# A10-A20-OLINUXINO-MICRO_Extension_Rev_A_.net
KiCad netlist of a schematic drawn in EAGLE
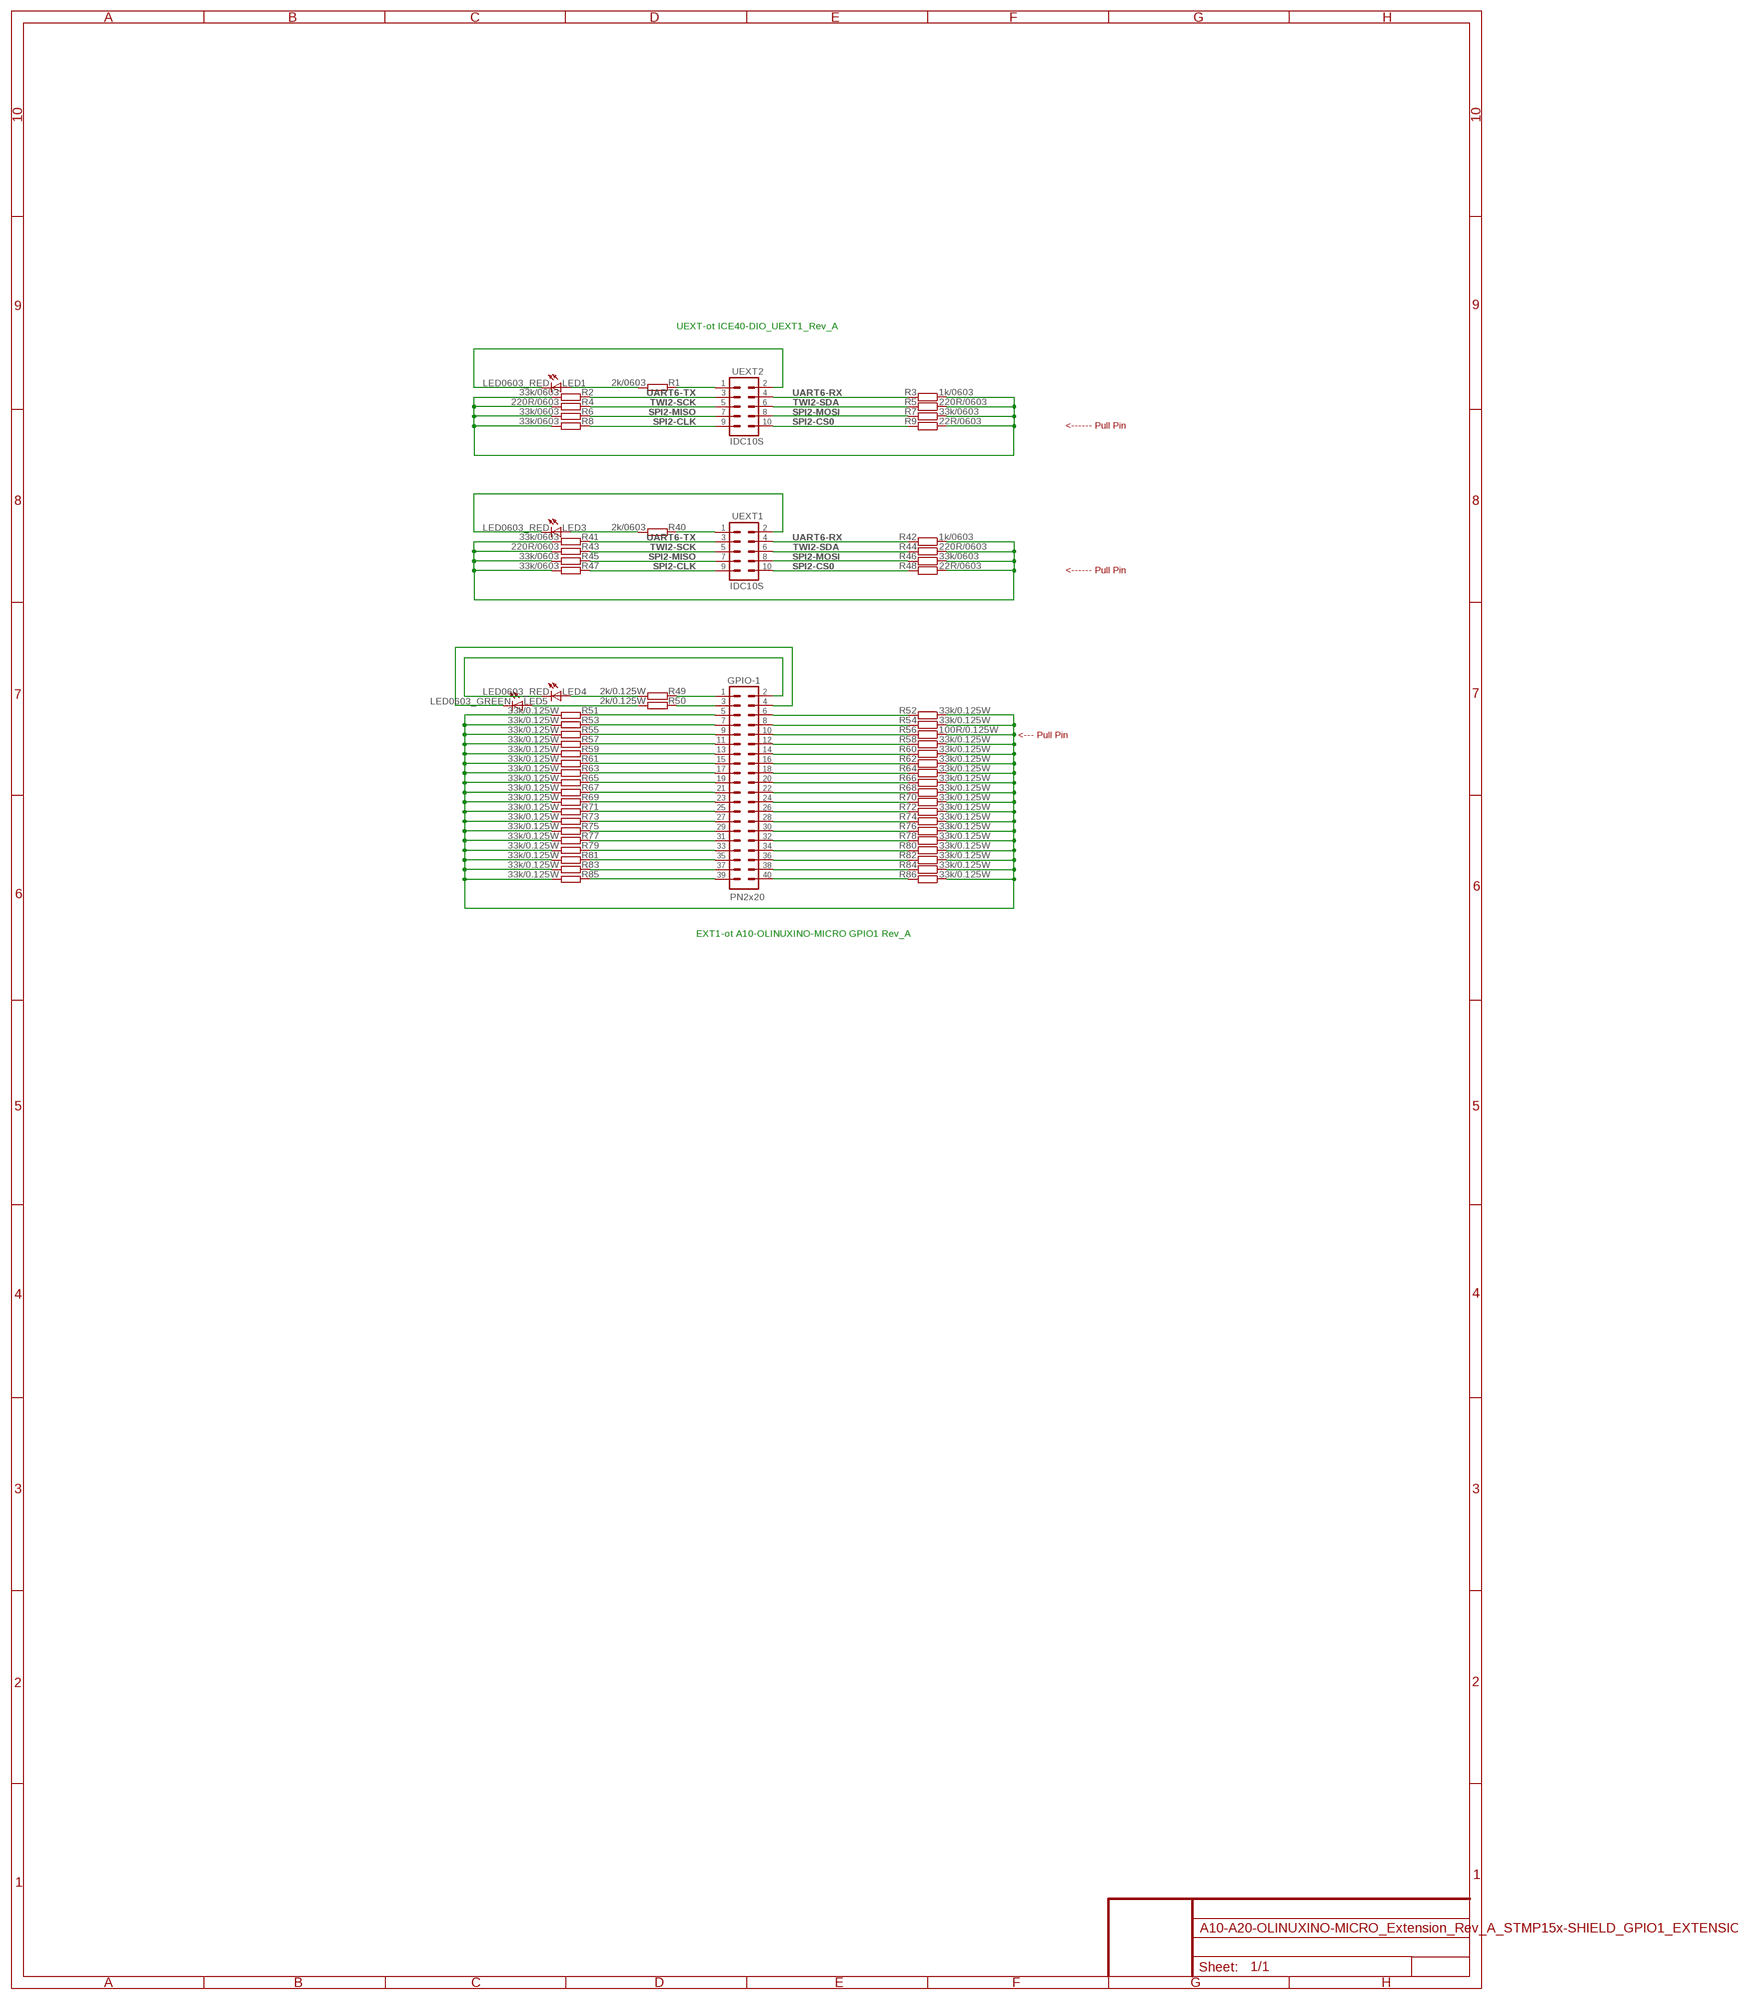
[diagram p0: schematic, sheet 1]

(export (version "E")
  (design (tool "Eeschema 10.0.6"))
  (components
    (comp (ref "GPIO-1")
      (value "PN2x20")
      (footprint "eagle-import:ML40-FEMALE(PN2X20)")
      (libsource (lib "eagle-import") (part "ML40PN2X20"))
    )
    (comp (ref "LED1")
      (value "LED0603_RED")
      (footprint "eagle-import:LED-0603")
      (libsource (lib "eagle-import") (part "LED0603DWS"))
    )
    (comp (ref "LED3")
      (value "LED0603_RED")
      (footprint "eagle-import:LED-0603")
      (libsource (lib "eagle-import") (part "LED0603DWS"))
    )
    (comp (ref "LED4")
      (value "LED0603_RED")
      (footprint "eagle-import:LED-0603")
      (libsource (lib "eagle-import") (part "LED0603DWS"))
    )
    (comp (ref "LED5")
      (value "LED0603_GREEN")
      (footprint "eagle-import:LED-0603")
      (libsource (lib "eagle-import") (part "LED0603DWS"))
    )
    (comp (ref "R1")
      (value "2k/0603")
      (footprint "eagle-import:0204_5")
      (libsource (lib "eagle-import") (part "R-EU_0204/5"))
    )
    (comp (ref "R2")
      (value "33k/0603")
      (footprint "eagle-import:0204_5")
      (libsource (lib "eagle-import") (part "R-EU_0204/5"))
    )
    (comp (ref "R3")
      (value "1k/0603")
      (footprint "eagle-import:0204_5")
      (libsource (lib "eagle-import") (part "R-EU_0204/5"))
    )
    (comp (ref "R4")
      (value "220R/0603")
      (footprint "eagle-import:0204_5")
      (libsource (lib "eagle-import") (part "R-EU_0204/5"))
    )
    (comp (ref "R5")
      (value "220R/0603")
      (footprint "eagle-import:0204_5")
      (libsource (lib "eagle-import") (part "R-EU_0204/5"))
    )
    (comp (ref "R6")
      (value "33k/0603")
      (footprint "eagle-import:0204_5")
      (libsource (lib "eagle-import") (part "R-EU_0204/5"))
    )
    (comp (ref "R7")
      (value "33k/0603")
      (footprint "eagle-import:0204_5")
      (libsource (lib "eagle-import") (part "R-EU_0204/5"))
    )
    (comp (ref "R8")
      (value "33k/0603")
      (footprint "eagle-import:0204_5")
      (libsource (lib "eagle-import") (part "R-EU_0204/5"))
    )
    (comp (ref "R9")
      (value "22R/0603")
      (footprint "eagle-import:0204_5")
      (libsource (lib "eagle-import") (part "R-EU_0204/5"))
    )
    (comp (ref "R40")
      (value "2k/0603")
      (footprint "eagle-import:0204_5")
      (libsource (lib "eagle-import") (part "R-EU_0204/5"))
    )
    (comp (ref "R41")
      (value "33k/0603")
      (footprint "eagle-import:0204_5")
      (libsource (lib "eagle-import") (part "R-EU_0204/5"))
    )
    (comp (ref "R42")
      (value "1k/0603")
      (footprint "eagle-import:0204_5")
      (libsource (lib "eagle-import") (part "R-EU_0204/5"))
    )
    (comp (ref "R43")
      (value "220R/0603")
      (footprint "eagle-import:0204_5")
      (libsource (lib "eagle-import") (part "R-EU_0204/5"))
    )
    (comp (ref "R44")
      (value "220R/0603")
      (footprint "eagle-import:0204_5")
      (libsource (lib "eagle-import") (part "R-EU_0204/5"))
    )
    (comp (ref "R45")
      (value "33k/0603")
      (footprint "eagle-import:0204_5")
      (libsource (lib "eagle-import") (part "R-EU_0204/5"))
    )
    (comp (ref "R46")
      (value "33k/0603")
      (footprint "eagle-import:0204_5")
      (libsource (lib "eagle-import") (part "R-EU_0204/5"))
    )
    (comp (ref "R47")
      (value "33k/0603")
      (footprint "eagle-import:0204_5")
      (libsource (lib "eagle-import") (part "R-EU_0204/5"))
    )
    (comp (ref "R48")
      (value "22R/0603")
      (footprint "eagle-import:0204_5")
      (libsource (lib "eagle-import") (part "R-EU_0204/5"))
    )
    (comp (ref "R49")
      (value "2k/0.125W")
      (footprint "eagle-import:0204_5")
      (libsource (lib "eagle-import") (part "R-EU_0204/5"))
    )
    (comp (ref "R50")
      (value "2k/0.125W")
      (footprint "eagle-import:0204_5")
      (libsource (lib "eagle-import") (part "R-EU_0204/5"))
    )
    (comp (ref "R51")
      (value "33k/0.125W")
      (footprint "eagle-import:0204_5")
      (libsource (lib "eagle-import") (part "R-EU_0204/5"))
    )
    (comp (ref "R52")
      (value "33k/0.125W")
      (footprint "eagle-import:0204_5")
      (libsource (lib "eagle-import") (part "R-EU_0204/5"))
    )
    (comp (ref "R53")
      (value "33k/0.125W")
      (footprint "eagle-import:0204_5")
      (libsource (lib "eagle-import") (part "R-EU_0204/5"))
    )
    (comp (ref "R54")
      (value "33k/0.125W")
      (footprint "eagle-import:0204_5")
      (libsource (lib "eagle-import") (part "R-EU_0204/5"))
    )
    (comp (ref "R55")
      (value "33k/0.125W")
      (footprint "eagle-import:0204_5")
      (libsource (lib "eagle-import") (part "R-EU_0204/5"))
    )
    (comp (ref "R56")
      (value "100R/0.125W")
      (footprint "eagle-import:0204_5")
      (libsource (lib "eagle-import") (part "R-EU_0204/5"))
    )
    (comp (ref "R57")
      (value "33k/0.125W")
      (footprint "eagle-import:0204_5")
      (libsource (lib "eagle-import") (part "R-EU_0204/5"))
    )
    (comp (ref "R58")
      (value "33k/0.125W")
      (footprint "eagle-import:0204_5")
      (libsource (lib "eagle-import") (part "R-EU_0204/5"))
    )
    (comp (ref "R59")
      (value "33k/0.125W")
      (footprint "eagle-import:0204_5")
      (libsource (lib "eagle-import") (part "R-EU_0204/5"))
    )
    (comp (ref "R60")
      (value "33k/0.125W")
      (footprint "eagle-import:0204_5")
      (libsource (lib "eagle-import") (part "R-EU_0204/5"))
    )
    (comp (ref "R61")
      (value "33k/0.125W")
      (footprint "eagle-import:0204_5")
      (libsource (lib "eagle-import") (part "R-EU_0204/5"))
    )
    (comp (ref "R62")
      (value "33k/0.125W")
      (footprint "eagle-import:0204_5")
      (libsource (lib "eagle-import") (part "R-EU_0204/5"))
    )
    (comp (ref "R63")
      (value "33k/0.125W")
      (footprint "eagle-import:0204_5")
      (libsource (lib "eagle-import") (part "R-EU_0204/5"))
    )
    (comp (ref "R64")
      (value "33k/0.125W")
      (footprint "eagle-import:0204_5")
      (libsource (lib "eagle-import") (part "R-EU_0204/5"))
    )
    (comp (ref "R65")
      (value "33k/0.125W")
      (footprint "eagle-import:0204_5")
      (libsource (lib "eagle-import") (part "R-EU_0204/5"))
    )
    (comp (ref "R66")
      (value "33k/0.125W")
      (footprint "eagle-import:0204_5")
      (libsource (lib "eagle-import") (part "R-EU_0204/5"))
    )
    (comp (ref "R67")
      (value "33k/0.125W")
      (footprint "eagle-import:0204_5")
      (libsource (lib "eagle-import") (part "R-EU_0204/5"))
    )
    (comp (ref "R68")
      (value "33k/0.125W")
      (footprint "eagle-import:0204_5")
      (libsource (lib "eagle-import") (part "R-EU_0204/5"))
    )
    (comp (ref "R69")
      (value "33k/0.125W")
      (footprint "eagle-import:0204_5")
      (libsource (lib "eagle-import") (part "R-EU_0204/5"))
    )
    (comp (ref "R70")
      (value "33k/0.125W")
      (footprint "eagle-import:0204_5")
      (libsource (lib "eagle-import") (part "R-EU_0204/5"))
    )
    (comp (ref "R71")
      (value "33k/0.125W")
      (footprint "eagle-import:0204_5")
      (libsource (lib "eagle-import") (part "R-EU_0204/5"))
    )
    (comp (ref "R72")
      (value "33k/0.125W")
      (footprint "eagle-import:0204_5")
      (libsource (lib "eagle-import") (part "R-EU_0204/5"))
    )
    (comp (ref "R73")
      (value "33k/0.125W")
      (footprint "eagle-import:0204_5")
      (libsource (lib "eagle-import") (part "R-EU_0204/5"))
    )
    (comp (ref "R74")
      (value "33k/0.125W")
      (footprint "eagle-import:0204_5")
      (libsource (lib "eagle-import") (part "R-EU_0204/5"))
    )
    (comp (ref "R75")
      (value "33k/0.125W")
      (footprint "eagle-import:0204_5")
      (libsource (lib "eagle-import") (part "R-EU_0204/5"))
    )
    (comp (ref "R76")
      (value "33k/0.125W")
      (footprint "eagle-import:0204_5")
      (libsource (lib "eagle-import") (part "R-EU_0204/5"))
    )
    (comp (ref "R77")
      (value "33k/0.125W")
      (footprint "eagle-import:0204_5")
      (libsource (lib "eagle-import") (part "R-EU_0204/5"))
    )
    (comp (ref "R78")
      (value "33k/0.125W")
      (footprint "eagle-import:0204_5")
      (libsource (lib "eagle-import") (part "R-EU_0204/5"))
    )
    (comp (ref "R79")
      (value "33k/0.125W")
      (footprint "eagle-import:0204_5")
      (libsource (lib "eagle-import") (part "R-EU_0204/5"))
    )
    (comp (ref "R80")
      (value "33k/0.125W")
      (footprint "eagle-import:0204_5")
      (libsource (lib "eagle-import") (part "R-EU_0204/5"))
    )
    (comp (ref "R81")
      (value "33k/0.125W")
      (footprint "eagle-import:0204_5")
      (libsource (lib "eagle-import") (part "R-EU_0204/5"))
    )
    (comp (ref "R82")
      (value "33k/0.125W")
      (footprint "eagle-import:0204_5")
      (libsource (lib "eagle-import") (part "R-EU_0204/5"))
    )
    (comp (ref "R83")
      (value "33k/0.125W")
      (footprint "eagle-import:0204_5")
      (libsource (lib "eagle-import") (part "R-EU_0204/5"))
    )
    (comp (ref "R84")
      (value "33k/0.125W")
      (footprint "eagle-import:0204_5")
      (libsource (lib "eagle-import") (part "R-EU_0204/5"))
    )
    (comp (ref "R85")
      (value "33k/0.125W")
      (footprint "eagle-import:0204_5")
      (libsource (lib "eagle-import") (part "R-EU_0204/5"))
    )
    (comp (ref "R86")
      (value "33k/0.125W")
      (footprint "eagle-import:0204_5")
      (libsource (lib "eagle-import") (part "R-EU_0204/5"))
    )
    (comp (ref "UEXT1")
      (value "IDC10S")
      (footprint "eagle-import:ML10-FEMALE(IDC10S_PCB)")
      (libsource (lib "eagle-import") (part "ML10ML10-FEMALE(IDC10S/PCB)"))
    )
    (comp (ref "UEXT2")
      (value "IDC10S")
      (footprint "eagle-import:ML10-FEMALE(IDC10S_PCB)")
      (libsource (lib "eagle-import") (part "ML10ML10-FEMALE(IDC10S/PCB)"))
    )
  )
  (nets
    (net (code "1") (name "/SPI2-CLK") (class "Default")
      (node (ref "R47") (pin "2") (pinfunction "2_2") (pintype "passive"))
      (node (ref "R8") (pin "2") (pinfunction "2_2") (pintype "passive"))
      (node (ref "UEXT1") (pin "9") (pinfunction "9_9") (pintype "passive"))
      (node (ref "UEXT2") (pin "9") (pinfunction "9_9") (pintype "passive"))
    )
    (net (code "2") (name "/SPI2-CS0") (class "Default")
      (node (ref "R48") (pin "2") (pinfunction "2_2") (pintype "passive"))
      (node (ref "R9") (pin "2") (pinfunction "2_2") (pintype "passive"))
      (node (ref "UEXT1") (pin "10") (pinfunction "10_10") (pintype "passive"))
      (node (ref "UEXT2") (pin "10") (pinfunction "10_10") (pintype "passive"))
    )
    (net (code "3") (name "/SPI2-MISO") (class "Default")
      (node (ref "R45") (pin "2") (pinfunction "2_2") (pintype "passive"))
      (node (ref "R6") (pin "2") (pinfunction "2_2") (pintype "passive"))
      (node (ref "UEXT1") (pin "7") (pinfunction "7_7") (pintype "passive"))
      (node (ref "UEXT2") (pin "7") (pinfunction "7_7") (pintype "passive"))
    )
    (net (code "4") (name "/SPI2-MOSI") (class "Default")
      (node (ref "R46") (pin "2") (pinfunction "2_2") (pintype "passive"))
      (node (ref "R7") (pin "2") (pinfunction "2_2") (pintype "passive"))
      (node (ref "UEXT1") (pin "8") (pinfunction "8_8") (pintype "passive"))
      (node (ref "UEXT2") (pin "8") (pinfunction "8_8") (pintype "passive"))
    )
    (net (code "5") (name "/TWI2-SCK") (class "Default")
      (node (ref "R4") (pin "2") (pinfunction "2_2") (pintype "passive"))
      (node (ref "R43") (pin "2") (pinfunction "2_2") (pintype "passive"))
      (node (ref "UEXT1") (pin "5") (pinfunction "5_5") (pintype "passive"))
      (node (ref "UEXT2") (pin "5") (pinfunction "5_5") (pintype "passive"))
    )
    (net (code "6") (name "/TWI2-SDA") (class "Default")
      (node (ref "R44") (pin "2") (pinfunction "2_2") (pintype "passive"))
      (node (ref "R5") (pin "2") (pinfunction "2_2") (pintype "passive"))
      (node (ref "UEXT1") (pin "6") (pinfunction "6_6") (pintype "passive"))
      (node (ref "UEXT2") (pin "6") (pinfunction "6_6") (pintype "passive"))
    )
    (net (code "7") (name "/UART6-RX") (class "Default")
      (node (ref "R3") (pin "2") (pinfunction "2_2") (pintype "passive"))
      (node (ref "R42") (pin "2") (pinfunction "2_2") (pintype "passive"))
      (node (ref "UEXT1") (pin "4") (pinfunction "4_4") (pintype "passive"))
      (node (ref "UEXT2") (pin "4") (pinfunction "4_4") (pintype "passive"))
    )
    (net (code "8") (name "/UART6-TX") (class "Default")
      (node (ref "R2") (pin "2") (pinfunction "2_2") (pintype "passive"))
      (node (ref "R41") (pin "2") (pinfunction "2_2") (pintype "passive"))
      (node (ref "UEXT1") (pin "3") (pinfunction "3_3") (pintype "passive"))
      (node (ref "UEXT2") (pin "3") (pinfunction "3_3") (pintype "passive"))
    )
    (net (code "9") (name "Net-(GPIO-1-Pad1)") (class "Default")
      (node (ref "GPIO-1") (pin "1") (pinfunction "1_1") (pintype "passive"))
      (node (ref "R49") (pin "2") (pinfunction "2_2") (pintype "passive"))
    )
    (net (code "10") (name "Net-(GPIO-1-Pad2)") (class "Default")
      (node (ref "GPIO-1") (pin "2") (pinfunction "2_2") (pintype "passive"))
      (node (ref "LED4") (pin "C") (pinfunction "C_C") (pintype "passive"))
    )
    (net (code "11") (name "Net-(GPIO-1-Pad3)") (class "Default")
      (node (ref "GPIO-1") (pin "3") (pinfunction "3_3") (pintype "passive"))
      (node (ref "R50") (pin "2") (pinfunction "2_2") (pintype "passive"))
    )
    (net (code "12") (name "Net-(GPIO-1-Pad4)") (class "Default")
      (node (ref "GPIO-1") (pin "4") (pinfunction "4_4") (pintype "passive"))
      (node (ref "LED5") (pin "C") (pinfunction "C_C") (pintype "passive"))
    )
    (net (code "13") (name "Net-(GPIO-1-Pad5)") (class "Default")
      (node (ref "GPIO-1") (pin "5") (pinfunction "5_5") (pintype "passive"))
      (node (ref "R51") (pin "2") (pinfunction "2_2") (pintype "passive"))
    )
    (net (code "14") (name "Net-(GPIO-1-Pad6)") (class "Default")
      (node (ref "GPIO-1") (pin "6") (pinfunction "6_6") (pintype "passive"))
      (node (ref "R52") (pin "2") (pinfunction "2_2") (pintype "passive"))
    )
    (net (code "15") (name "Net-(GPIO-1-Pad7)") (class "Default")
      (node (ref "GPIO-1") (pin "7") (pinfunction "7_7") (pintype "passive"))
      (node (ref "R53") (pin "2") (pinfunction "2_2") (pintype "passive"))
    )
    (net (code "16") (name "Net-(GPIO-1-Pad8)") (class "Default")
      (node (ref "GPIO-1") (pin "8") (pinfunction "8_8") (pintype "passive"))
      (node (ref "R54") (pin "2") (pinfunction "2_2") (pintype "passive"))
    )
    (net (code "17") (name "Net-(GPIO-1-Pad9)") (class "Default")
      (node (ref "GPIO-1") (pin "9") (pinfunction "9_9") (pintype "passive"))
      (node (ref "R55") (pin "2") (pinfunction "2_2") (pintype "passive"))
    )
    (net (code "18") (name "Net-(GPIO-1-Pad10)") (class "Default")
      (node (ref "GPIO-1") (pin "10") (pinfunction "10_10") (pintype "passive"))
      (node (ref "R56") (pin "2") (pinfunction "2_2") (pintype "passive"))
    )
    (net (code "19") (name "Net-(GPIO-1-Pad11)") (class "Default")
      (node (ref "GPIO-1") (pin "11") (pinfunction "11_11") (pintype "passive"))
      (node (ref "R57") (pin "2") (pinfunction "2_2") (pintype "passive"))
    )
    (net (code "20") (name "Net-(GPIO-1-Pad12)") (class "Default")
      (node (ref "GPIO-1") (pin "12") (pinfunction "12_12") (pintype "passive"))
      (node (ref "R58") (pin "2") (pinfunction "2_2") (pintype "passive"))
    )
    (net (code "21") (name "Net-(GPIO-1-Pad13)") (class "Default")
      (node (ref "GPIO-1") (pin "13") (pinfunction "13_13") (pintype "passive"))
      (node (ref "R59") (pin "2") (pinfunction "2_2") (pintype "passive"))
    )
    (net (code "22") (name "Net-(GPIO-1-Pad14)") (class "Default")
      (node (ref "GPIO-1") (pin "14") (pinfunction "14_14") (pintype "passive"))
      (node (ref "R60") (pin "2") (pinfunction "2_2") (pintype "passive"))
    )
    (net (code "23") (name "Net-(GPIO-1-Pad15)") (class "Default")
      (node (ref "GPIO-1") (pin "15") (pinfunction "15_15") (pintype "passive"))
      (node (ref "R61") (pin "2") (pinfunction "2_2") (pintype "passive"))
    )
    (net (code "24") (name "Net-(GPIO-1-Pad16)") (class "Default")
      (node (ref "GPIO-1") (pin "16") (pinfunction "16_16") (pintype "passive"))
      (node (ref "R62") (pin "2") (pinfunction "2_2") (pintype "passive"))
    )
    (net (code "25") (name "Net-(GPIO-1-Pad17)") (class "Default")
      (node (ref "GPIO-1") (pin "17") (pinfunction "17_17") (pintype "passive"))
      (node (ref "R63") (pin "2") (pinfunction "2_2") (pintype "passive"))
    )
    (net (code "26") (name "Net-(GPIO-1-Pad18)") (class "Default")
      (node (ref "GPIO-1") (pin "18") (pinfunction "18_18") (pintype "passive"))
      (node (ref "R64") (pin "2") (pinfunction "2_2") (pintype "passive"))
    )
    (net (code "27") (name "Net-(GPIO-1-Pad19)") (class "Default")
      (node (ref "GPIO-1") (pin "19") (pinfunction "19_19") (pintype "passive"))
      (node (ref "R65") (pin "2") (pinfunction "2_2") (pintype "passive"))
    )
    (net (code "28") (name "Net-(GPIO-1-Pad20)") (class "Default")
      (node (ref "GPIO-1") (pin "20") (pinfunction "20_20") (pintype "passive"))
      (node (ref "R66") (pin "2") (pinfunction "2_2") (pintype "passive"))
    )
    (net (code "29") (name "Net-(GPIO-1-Pad21)") (class "Default")
      (node (ref "GPIO-1") (pin "21") (pinfunction "21_21") (pintype "passive"))
      (node (ref "R67") (pin "2") (pinfunction "2_2") (pintype "passive"))
    )
    (net (code "30") (name "Net-(GPIO-1-Pad22)") (class "Default")
      (node (ref "GPIO-1") (pin "22") (pinfunction "22_22") (pintype "passive"))
      (node (ref "R68") (pin "2") (pinfunction "2_2") (pintype "passive"))
    )
    (net (code "31") (name "Net-(GPIO-1-Pad23)") (class "Default")
      (node (ref "GPIO-1") (pin "23") (pinfunction "23_23") (pintype "passive"))
      (node (ref "R69") (pin "2") (pinfunction "2_2") (pintype "passive"))
    )
    (net (code "32") (name "Net-(GPIO-1-Pad24)") (class "Default")
      (node (ref "GPIO-1") (pin "24") (pinfunction "24_24") (pintype "passive"))
      (node (ref "R70") (pin "2") (pinfunction "2_2") (pintype "passive"))
    )
    (net (code "33") (name "Net-(GPIO-1-Pad25)") (class "Default")
      (node (ref "GPIO-1") (pin "25") (pinfunction "25_25") (pintype "passive"))
      (node (ref "R71") (pin "2") (pinfunction "2_2") (pintype "passive"))
    )
    (net (code "34") (name "Net-(GPIO-1-Pad26)") (class "Default")
      (node (ref "GPIO-1") (pin "26") (pinfunction "26_26") (pintype "passive"))
      (node (ref "R72") (pin "2") (pinfunction "2_2") (pintype "passive"))
    )
    (net (code "35") (name "Net-(GPIO-1-Pad27)") (class "Default")
      (node (ref "GPIO-1") (pin "27") (pinfunction "27_27") (pintype "passive"))
      (node (ref "R73") (pin "2") (pinfunction "2_2") (pintype "passive"))
    )
    (net (code "36") (name "Net-(GPIO-1-Pad28)") (class "Default")
      (node (ref "GPIO-1") (pin "28") (pinfunction "28_28") (pintype "passive"))
      (node (ref "R74") (pin "2") (pinfunction "2_2") (pintype "passive"))
    )
    (net (code "37") (name "Net-(GPIO-1-Pad29)") (class "Default")
      (node (ref "GPIO-1") (pin "29") (pinfunction "29_29") (pintype "passive"))
      (node (ref "R75") (pin "2") (pinfunction "2_2") (pintype "passive"))
    )
    (net (code "38") (name "Net-(GPIO-1-Pad30)") (class "Default")
      (node (ref "GPIO-1") (pin "30") (pinfunction "30_30") (pintype "passive"))
      (node (ref "R76") (pin "2") (pinfunction "2_2") (pintype "passive"))
    )
    (net (code "39") (name "Net-(GPIO-1-Pad31)") (class "Default")
      (node (ref "GPIO-1") (pin "31") (pinfunction "31_31") (pintype "passive"))
      (node (ref "R77") (pin "2") (pinfunction "2_2") (pintype "passive"))
    )
    (net (code "40") (name "Net-(GPIO-1-Pad32)") (class "Default")
      (node (ref "GPIO-1") (pin "32") (pinfunction "32_32") (pintype "passive"))
      (node (ref "R78") (pin "2") (pinfunction "2_2") (pintype "passive"))
    )
    (net (code "41") (name "Net-(GPIO-1-Pad33)") (class "Default")
      (node (ref "GPIO-1") (pin "33") (pinfunction "33_33") (pintype "passive"))
      (node (ref "R79") (pin "2") (pinfunction "2_2") (pintype "passive"))
    )
    (net (code "42") (name "Net-(GPIO-1-Pad34)") (class "Default")
      (node (ref "GPIO-1") (pin "34") (pinfunction "34_34") (pintype "passive"))
      (node (ref "R80") (pin "2") (pinfunction "2_2") (pintype "passive"))
    )
    (net (code "43") (name "Net-(GPIO-1-Pad35)") (class "Default")
      (node (ref "GPIO-1") (pin "35") (pinfunction "35_35") (pintype "passive"))
      (node (ref "R81") (pin "2") (pinfunction "2_2") (pintype "passive"))
    )
    (net (code "44") (name "Net-(GPIO-1-Pad36)") (class "Default")
      (node (ref "GPIO-1") (pin "36") (pinfunction "36_36") (pintype "passive"))
      (node (ref "R82") (pin "2") (pinfunction "2_2") (pintype "passive"))
    )
    (net (code "45") (name "Net-(GPIO-1-Pad37)") (class "Default")
      (node (ref "GPIO-1") (pin "37") (pinfunction "37_37") (pintype "passive"))
      (node (ref "R83") (pin "2") (pinfunction "2_2") (pintype "passive"))
    )
    (net (code "46") (name "Net-(GPIO-1-Pad38)") (class "Default")
      (node (ref "GPIO-1") (pin "38") (pinfunction "38_38") (pintype "passive"))
      (node (ref "R84") (pin "2") (pinfunction "2_2") (pintype "passive"))
    )
    (net (code "47") (name "Net-(GPIO-1-Pad39)") (class "Default")
      (node (ref "GPIO-1") (pin "39") (pinfunction "39_39") (pintype "passive"))
      (node (ref "R85") (pin "2") (pinfunction "2_2") (pintype "passive"))
    )
    (net (code "48") (name "Net-(GPIO-1-Pad40)") (class "Default")
      (node (ref "GPIO-1") (pin "40") (pinfunction "40_40") (pintype "passive"))
      (node (ref "R86") (pin "2") (pinfunction "2_2") (pintype "passive"))
    )
    (net (code "49") (name "Net-(LED1-PadA)") (class "Default")
      (node (ref "LED1") (pin "A") (pinfunction "A_A") (pintype "passive"))
      (node (ref "R1") (pin "1") (pinfunction "1_1") (pintype "passive"))
    )
    (net (code "50") (name "Net-(LED1-PadC)") (class "Default")
      (node (ref "LED1") (pin "C") (pinfunction "C_C") (pintype "passive"))
      (node (ref "UEXT2") (pin "2") (pinfunction "2_2") (pintype "passive"))
    )
    (net (code "51") (name "Net-(LED3-PadA)") (class "Default")
      (node (ref "LED3") (pin "A") (pinfunction "A_A") (pintype "passive"))
      (node (ref "R40") (pin "1") (pinfunction "1_1") (pintype "passive"))
    )
    (net (code "52") (name "Net-(LED3-PadC)") (class "Default")
      (node (ref "LED3") (pin "C") (pinfunction "C_C") (pintype "passive"))
      (node (ref "UEXT1") (pin "2") (pinfunction "2_2") (pintype "passive"))
    )
    (net (code "53") (name "Net-(LED4-PadA)") (class "Default")
      (node (ref "LED4") (pin "A") (pinfunction "A_A") (pintype "passive"))
      (node (ref "R49") (pin "1") (pinfunction "1_1") (pintype "passive"))
    )
    (net (code "54") (name "Net-(LED5-PadA)") (class "Default")
      (node (ref "LED5") (pin "A") (pinfunction "A_A") (pintype "passive"))
      (node (ref "R50") (pin "1") (pinfunction "1_1") (pintype "passive"))
    )
    (net (code "55") (name "Net-(R1-Pad2)") (class "Default")
      (node (ref "R1") (pin "2") (pinfunction "2_2") (pintype "passive"))
      (node (ref "UEXT2") (pin "1") (pinfunction "1_1") (pintype "passive"))
    )
    (net (code "56") (name "Net-(R2-Pad1)") (class "Default")
      (node (ref "R2") (pin "1") (pinfunction "1_1") (pintype "passive"))
      (node (ref "R3") (pin "1") (pinfunction "1_1") (pintype "passive"))
      (node (ref "R4") (pin "1") (pinfunction "1_1") (pintype "passive"))
      (node (ref "R5") (pin "1") (pinfunction "1_1") (pintype "passive"))
      (node (ref "R6") (pin "1") (pinfunction "1_1") (pintype "passive"))
      (node (ref "R7") (pin "1") (pinfunction "1_1") (pintype "passive"))
      (node (ref "R8") (pin "1") (pinfunction "1_1") (pintype "passive"))
      (node (ref "R9") (pin "1") (pinfunction "1_1") (pintype "passive"))
    )
    (net (code "57") (name "Net-(R40-Pad2)") (class "Default")
      (node (ref "R40") (pin "2") (pinfunction "2_2") (pintype "passive"))
      (node (ref "UEXT1") (pin "1") (pinfunction "1_1") (pintype "passive"))
    )
    (net (code "58") (name "Net-(R41-Pad1)") (class "Default")
      (node (ref "R41") (pin "1") (pinfunction "1_1") (pintype "passive"))
      (node (ref "R42") (pin "1") (pinfunction "1_1") (pintype "passive"))
      (node (ref "R43") (pin "1") (pinfunction "1_1") (pintype "passive"))
      (node (ref "R44") (pin "1") (pinfunction "1_1") (pintype "passive"))
      (node (ref "R45") (pin "1") (pinfunction "1_1") (pintype "passive"))
      (node (ref "R46") (pin "1") (pinfunction "1_1") (pintype "passive"))
      (node (ref "R47") (pin "1") (pinfunction "1_1") (pintype "passive"))
      (node (ref "R48") (pin "1") (pinfunction "1_1") (pintype "passive"))
    )
    (net (code "59") (name "Net-(R51-Pad1)") (class "Default")
      (node (ref "R51") (pin "1") (pinfunction "1_1") (pintype "passive"))
      (node (ref "R52") (pin "1") (pinfunction "1_1") (pintype "passive"))
      (node (ref "R53") (pin "1") (pinfunction "1_1") (pintype "passive"))
      (node (ref "R54") (pin "1") (pinfunction "1_1") (pintype "passive"))
      (node (ref "R55") (pin "1") (pinfunction "1_1") (pintype "passive"))
      (node (ref "R56") (pin "1") (pinfunction "1_1") (pintype "passive"))
      (node (ref "R57") (pin "1") (pinfunction "1_1") (pintype "passive"))
      (node (ref "R58") (pin "1") (pinfunction "1_1") (pintype "passive"))
      (node (ref "R59") (pin "1") (pinfunction "1_1") (pintype "passive"))
      (node (ref "R60") (pin "1") (pinfunction "1_1") (pintype "passive"))
      (node (ref "R61") (pin "1") (pinfunction "1_1") (pintype "passive"))
      (node (ref "R62") (pin "1") (pinfunction "1_1") (pintype "passive"))
      (node (ref "R63") (pin "1") (pinfunction "1_1") (pintype "passive"))
      (node (ref "R64") (pin "1") (pinfunction "1_1") (pintype "passive"))
      (node (ref "R65") (pin "1") (pinfunction "1_1") (pintype "passive"))
      (node (ref "R66") (pin "1") (pinfunction "1_1") (pintype "passive"))
      (node (ref "R67") (pin "1") (pinfunction "1_1") (pintype "passive"))
      (node (ref "R68") (pin "1") (pinfunction "1_1") (pintype "passive"))
      (node (ref "R69") (pin "1") (pinfunction "1_1") (pintype "passive"))
      (node (ref "R70") (pin "1") (pinfunction "1_1") (pintype "passive"))
      (node (ref "R71") (pin "1") (pinfunction "1_1") (pintype "passive"))
      (node (ref "R72") (pin "1") (pinfunction "1_1") (pintype "passive"))
      (node (ref "R73") (pin "1") (pinfunction "1_1") (pintype "passive"))
      (node (ref "R74") (pin "1") (pinfunction "1_1") (pintype "passive"))
      (node (ref "R75") (pin "1") (pinfunction "1_1") (pintype "passive"))
      (node (ref "R76") (pin "1") (pinfunction "1_1") (pintype "passive"))
      (node (ref "R77") (pin "1") (pinfunction "1_1") (pintype "passive"))
      (node (ref "R78") (pin "1") (pinfunction "1_1") (pintype "passive"))
      (node (ref "R79") (pin "1") (pinfunction "1_1") (pintype "passive"))
      (node (ref "R80") (pin "1") (pinfunction "1_1") (pintype "passive"))
      (node (ref "R81") (pin "1") (pinfunction "1_1") (pintype "passive"))
      (node (ref "R82") (pin "1") (pinfunction "1_1") (pintype "passive"))
      (node (ref "R83") (pin "1") (pinfunction "1_1") (pintype "passive"))
      (node (ref "R84") (pin "1") (pinfunction "1_1") (pintype "passive"))
      (node (ref "R85") (pin "1") (pinfunction "1_1") (pintype "passive"))
      (node (ref "R86") (pin "1") (pinfunction "1_1") (pintype "passive"))
    )
  )
)
